# TeachingInstrument_power_supply_v2.net
KiCad netlist of a schematic drawn in EAGLE
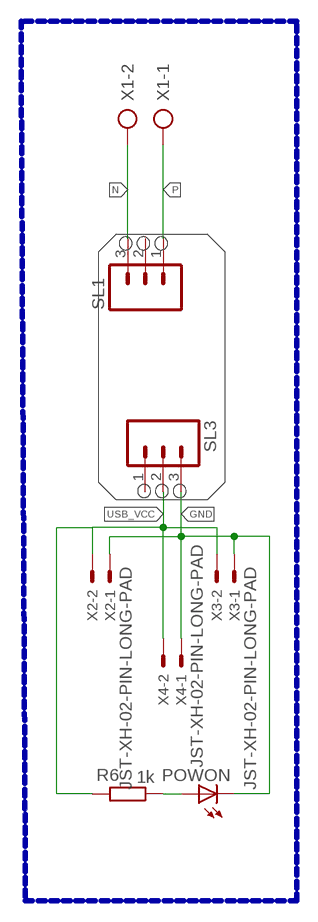
[diagram p0: schematic, sheet 1]

(export (version "E")
  (design (tool "Eeschema 10.0.6"))
  (components
    (comp (ref "POWON")
      (value "LED3MM")
      (footprint "eagle-import:LED3MM")
      (libsource (lib "eagle-import") (part "LED3MM"))
    )
    (comp (ref "R6")
      (value "1k")
      (footprint "eagle-import:0204_7")
      (libsource (lib "eagle-import") (part "R-EU_0204/7"))
    )
    (comp (ref "SL1")
      (value "M03")
      (footprint "eagle-import:03P")
      (libsource (lib "eagle-import") (part "M03"))
    )
    (comp (ref "SL3")
      (value "M03")
      (footprint "eagle-import:03P")
      (libsource (lib "eagle-import") (part "M03"))
    )
    (comp (ref "X1")
      (value "AK500/2-H")
      (footprint "eagle-import:AK500_2-H")
      (libsource (lib "eagle-import") (part "AK500/2-H"))
    )
    (comp (ref "X2")
      (value "JST-XH-02-PIN-LONG-PAD")
      (footprint "eagle-import:JST-XH-02-PACKAGE-LONG-PAD")
      (libsource (lib "eagle-import") (part "JST-XH-02-PIN-LONG-PAD"))
    )
    (comp (ref "X3")
      (value "JST-XH-02-PIN-LONG-PAD")
      (footprint "eagle-import:JST-XH-02-PACKAGE-LONG-PAD")
      (libsource (lib "eagle-import") (part "JST-XH-02-PIN-LONG-PAD"))
    )
    (comp (ref "X4")
      (value "JST-XH-02-PIN-LONG-PAD")
      (footprint "eagle-import:JST-XH-02-PACKAGE-LONG-PAD")
      (libsource (lib "eagle-import") (part "JST-XH-02-PIN-LONG-PAD"))
    )
  )
  (nets
    (net (code "1") (name "GND") (class "Default")
      (node (ref "POWON") (pin "K") (pinfunction "C_K") (pintype "passive"))
      (node (ref "SL3") (pin "3") (pinfunction "3_3") (pintype "passive"))
      (node (ref "X2") (pin "1") (pinfunction "S_1") (pintype "passive"))
      (node (ref "X3") (pin "1") (pinfunction "S_1") (pintype "passive"))
      (node (ref "X4") (pin "1") (pinfunction "S_1") (pintype "passive"))
    )
    (net (code "2") (name "N") (class "Default")
      (node (ref "SL1") (pin "3") (pinfunction "3_3") (pintype "passive"))
      (node (ref "X1") (pin "2") (pinfunction "KL_2") (pintype "passive"))
    )
    (net (code "3") (name "Net-(POWON-PadA)") (class "Default")
      (node (ref "POWON") (pin "A") (pinfunction "A_A") (pintype "passive"))
      (node (ref "R6") (pin "1") (pinfunction "1_1") (pintype "passive"))
    )
    (net (code "4") (name "P") (class "Default")
      (node (ref "SL1") (pin "1") (pinfunction "1_1") (pintype "passive"))
      (node (ref "X1") (pin "1") (pinfunction "KL_1") (pintype "passive"))
    )
    (net (code "5") (name "USB_VCC") (class "Default")
      (node (ref "R6") (pin "2") (pinfunction "2_2") (pintype "passive"))
      (node (ref "SL3") (pin "2") (pinfunction "2_2") (pintype "passive"))
      (node (ref "X2") (pin "2") (pinfunction "S_2") (pintype "passive"))
      (node (ref "X3") (pin "2") (pinfunction "S_2") (pintype "passive"))
      (node (ref "X4") (pin "2") (pinfunction "S_2") (pintype "passive"))
    )
    (net (code "6") (name "unconnected-(SL1-Pad2)") (class "Default")
      (node (ref "SL1") (pin "2") (pinfunction "2_2") (pintype "passive"))
    )
    (net (code "7") (name "unconnected-(SL3-Pad1)") (class "Default")
      (node (ref "SL3") (pin "1") (pinfunction "1_1") (pintype "passive"))
    )
  )
)
